# ACmonitor.net
KiCad netlist of a schematic drawn in Altium Designer
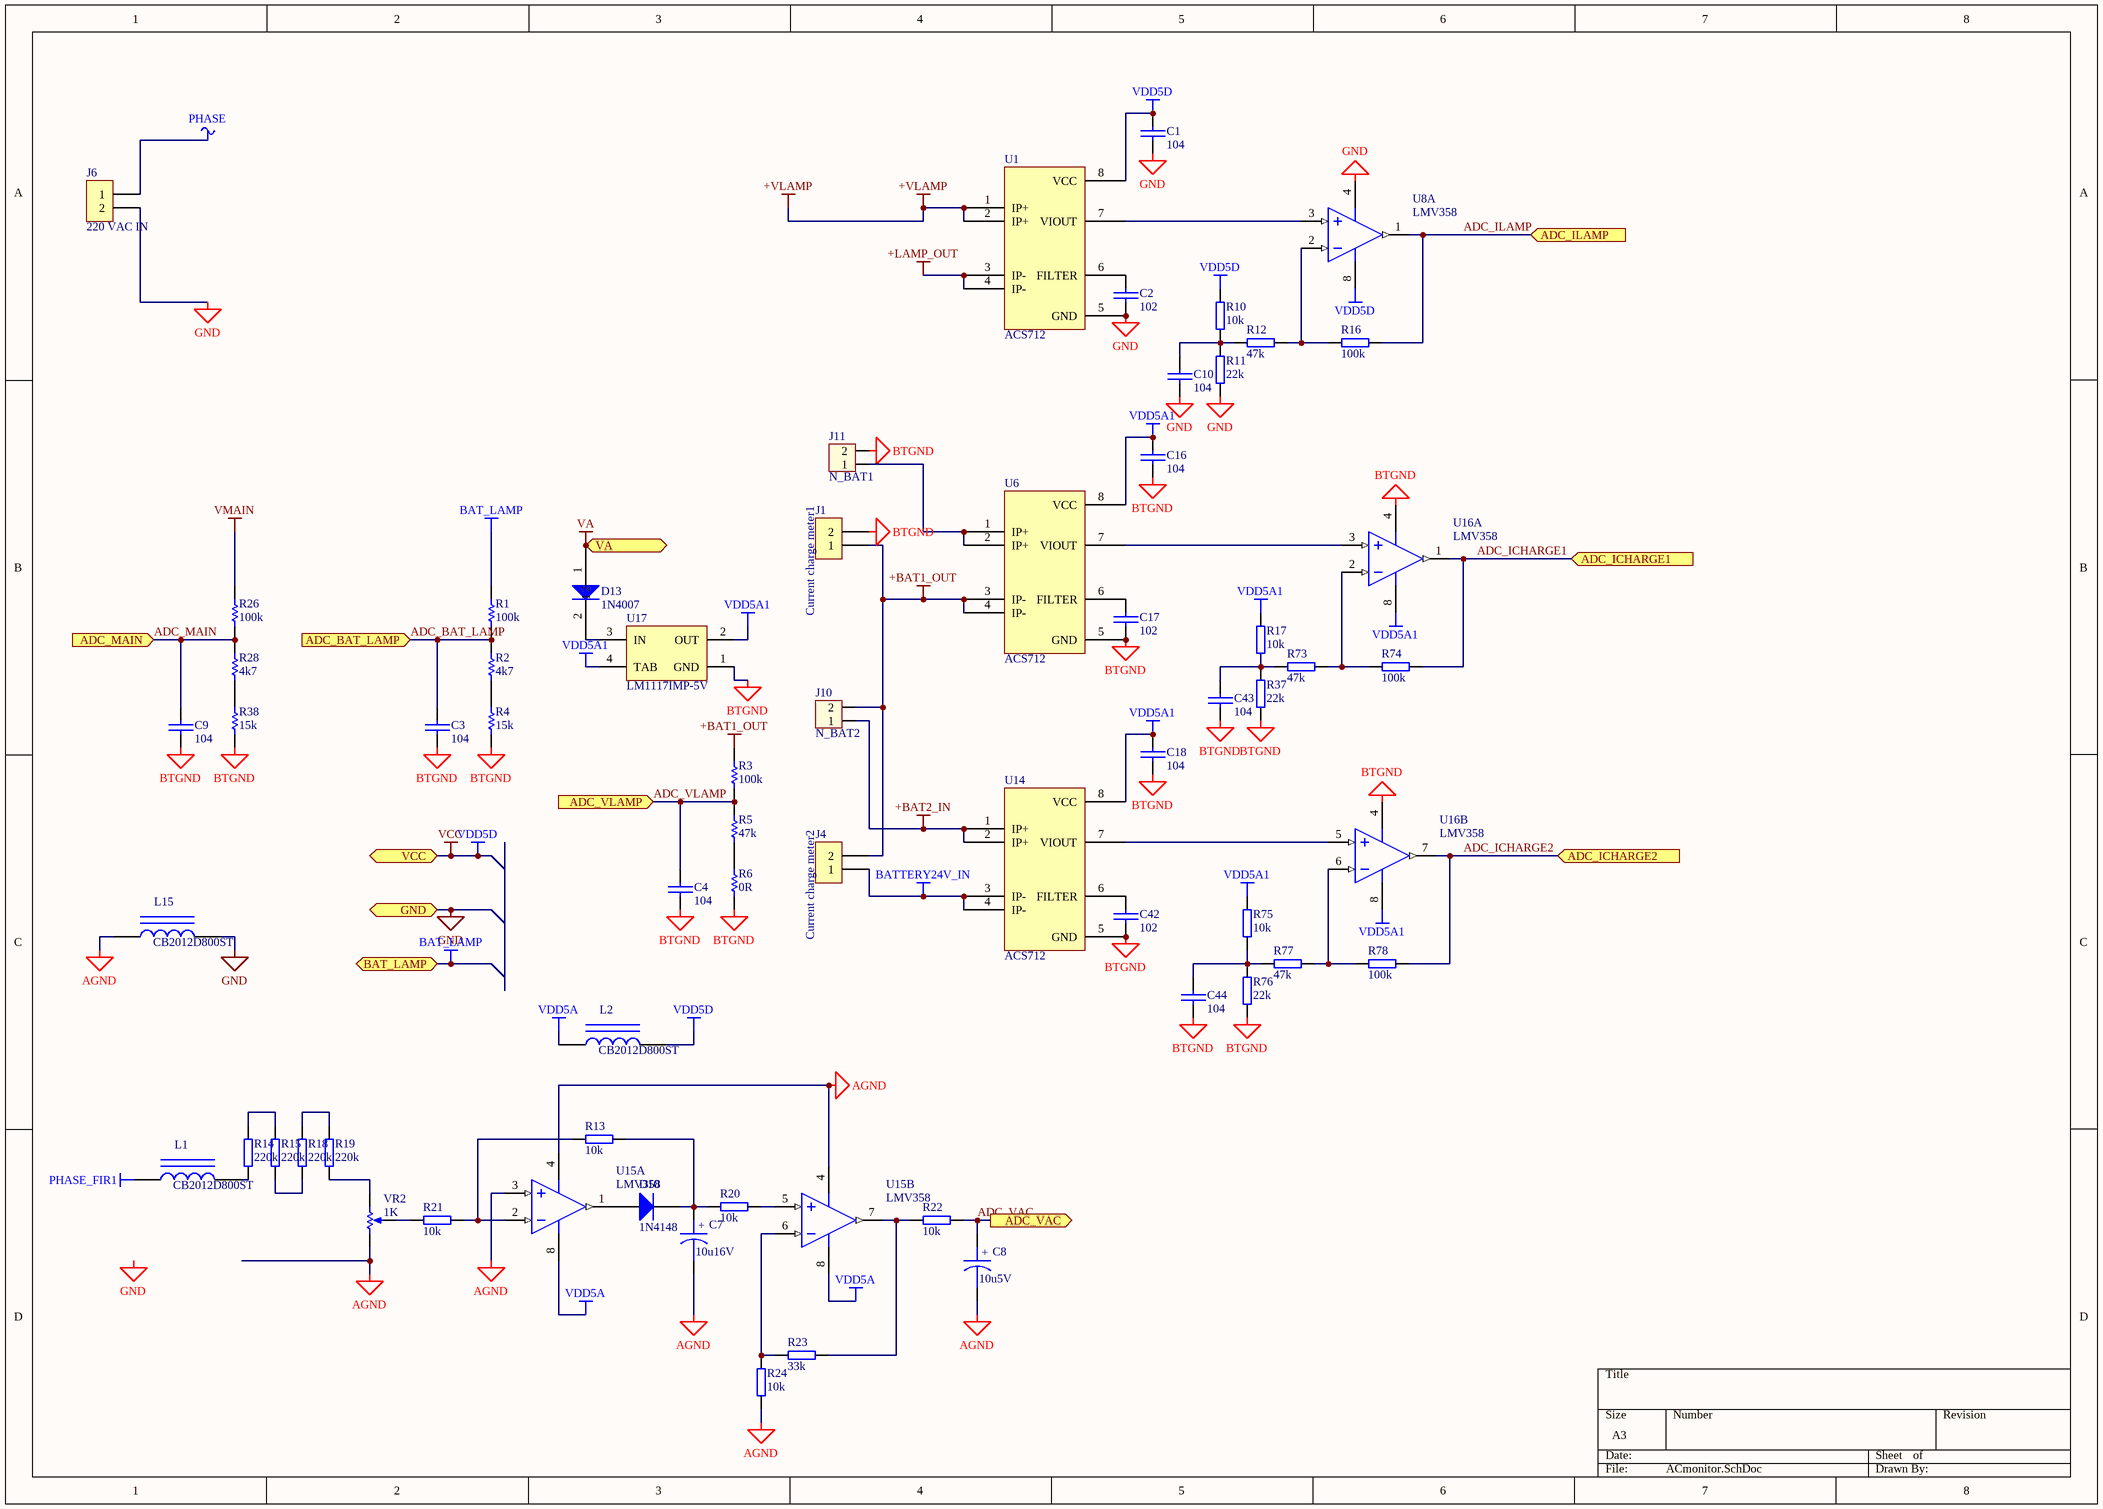
[diagram p0: ACmonitor.SchDoc]

(export (version "E")
  (design (tool "Eeschema 10.0.6"))
  (components
    (comp (ref "C1")
      (value "104")
      (footprint "C6-0805_N")
      (description "Capacitor")
      (libsource (lib "*") (part "CAP"))
    )
    (comp (ref "C2")
      (value "102")
      (footprint "C6-0805_N")
      (description "Capacitor")
      (libsource (lib "*") (part "CAP"))
    )
    (comp (ref "C3")
      (value "104")
      (footprint "C6-0805_N")
      (description "Capacitor")
      (libsource (lib "*") (part "CAP"))
    )
    (comp (ref "C4")
      (value "104")
      (footprint "C6-0805_N")
      (description "Capacitor")
      (libsource (lib "*") (part "CAP"))
    )
    (comp (ref "C7")
      (value "10u16V")
      (footprint "CAPMP7343X310N")
      (description "Capacitor")
      (libsource (lib "*") (part "CAPACITOR POL"))
    )
    (comp (ref "C8")
      (value "10u5V")
      (footprint "CAPMP3528X210N")
      (description "Capacitor")
      (libsource (lib "*") (part "CAPACITOR POL"))
    )
    (comp (ref "C9")
      (value "104")
      (footprint "C6-0805_N")
      (description "Capacitor")
      (libsource (lib "*") (part "CAP"))
    )
    (comp (ref "C10")
      (value "104")
      (footprint "C6-0805_N")
      (description "Capacitor")
      (libsource (lib "*") (part "CAP"))
    )
    (comp (ref "C16")
      (value "104")
      (footprint "C6-0805_N")
      (description "Capacitor")
      (libsource (lib "*") (part "CAP"))
    )
    (comp (ref "C17")
      (value "102")
      (footprint "C6-0805_N")
      (description "Capacitor")
      (libsource (lib "*") (part "CAP"))
    )
    (comp (ref "C18")
      (value "104")
      (footprint "C6-0805_N")
      (description "Capacitor")
      (libsource (lib "*") (part "CAP"))
    )
    (comp (ref "C42")
      (value "102")
      (footprint "C6-0805_N")
      (description "Capacitor")
      (libsource (lib "*") (part "CAP"))
    )
    (comp (ref "C43")
      (value "104")
      (footprint "C6-0805_N")
      (description "Capacitor")
      (libsource (lib "*") (part "CAP"))
    )
    (comp (ref "C44")
      (value "104")
      (footprint "C6-0805_N")
      (description "Capacitor")
      (libsource (lib "*") (part "CAP"))
    )
    (comp (ref "D10")
      (value "1N4148")
      (footprint "SOD80, LL-34")
      (description "1 Amp General Purpose Rectifier")
      (fields (field (name "PUBLISHER") "Altium Limited"))
      (libsource (lib "*") (part "Diode 1N4007"))
    )
    (comp (ref "D13") (value "1N4007") (footprint "DO-214AA") (libsource (lib "*") (part "DIODE")))
    (comp (ref "J1")
      (value "Current charge meter1")
      (footprint "TERMINAL2")
      (description "Connector")
      (libsource (lib "") (part "CON2_1"))
    )
    (comp (ref "J4")
      (value "Current charge meter2")
      (footprint "TERMINAL2")
      (description "Connector")
      (libsource (lib "") (part "CON2_1"))
    )
    (comp (ref "J6")
      (value "220 VAC IN")
      (footprint "TERMINAL2")
      (description "Connector")
      (libsource (lib "*") (part "CON2"))
    )
    (comp (ref "J10")
      (value "N_BAT2")
      (footprint "TERMINAL2")
      (description "Connector 2")
      (libsource (lib "syhaunguyen") (part "Con2"))
    )
    (comp (ref "J11")
      (value "N_BAT1")
      (footprint "TERMINAL2")
      (description "Connector 2")
      (libsource (lib "syhaunguyen") (part "Con2"))
    )
    (comp (ref "L1")
      (value "CB2012D800ST")
      (footprint "R6-0805_N")
      (description "80 Ohm SMD-0805 Chip Ferrite Bead")
      (libsource (lib "*") (part "INDUCTOR IRON"))
    )
    (comp (ref "L2")
      (value "CB2012D800ST")
      (footprint "R6-0805_N")
      (description "80 Ohm SMD-0805 Chip Ferrite Bead")
      (libsource (lib "*") (part "INDUCTOR IRON"))
    )
    (comp (ref "L15")
      (value "CB2012D800ST")
      (footprint "R6-0805_N")
      (description "80 Ohm SMD-0805 Chip Ferrite Bead")
      (libsource (lib "*") (part "INDUCTOR IRON"))
    )
    (comp (ref "R1")
      (value "100k")
      (footprint "6-0805_N")
      (description "Semiconductor Resistor")
      (fields (field (name "PUBLISHER") "*"))
      (libsource (lib "*") (part "Res Semi"))
    )
    (comp (ref "R2")
      (value "4k7")
      (footprint "6-0805_N")
      (description "Semiconductor Resistor")
      (fields (field (name "PUBLISHER") "*"))
      (libsource (lib "*") (part "Res Semi"))
    )
    (comp (ref "R3")
      (value "100k")
      (footprint "6-0805_N")
      (description "Semiconductor Resistor")
      (fields (field (name "PUBLISHER") "*"))
      (libsource (lib "*") (part "Res Semi"))
    )
    (comp (ref "R4")
      (value "15k")
      (footprint "6-0805_N")
      (description "Semiconductor Resistor")
      (fields (field (name "PUBLISHER") "*"))
      (libsource (lib "*") (part "Res Semi"))
    )
    (comp (ref "R5")
      (value "47k")
      (footprint "6-0805_N")
      (description "Semiconductor Resistor")
      (fields (field (name "PUBLISHER") "*"))
      (libsource (lib "*") (part "Res Semi"))
    )
    (comp (ref "R6")
      (value "0R")
      (footprint "6-0805_N")
      (description "Semiconductor Resistor")
      (fields (field (name "PUBLISHER") "*"))
      (libsource (lib "*") (part "Res Semi"))
    )
    (comp (ref "R10") (value "10k") (footprint "6-0805_N") (libsource (lib "*") (part "RES2")))
    (comp (ref "R11") (value "22k") (footprint "6-0805_N") (libsource (lib "*") (part "RES2")))
    (comp (ref "R12") (value "47k") (footprint "6-0805_N") (libsource (lib "*") (part "RES2")))
    (comp (ref "R13") (value "10k") (footprint "6-0805_N") (libsource (lib "*") (part "RES2")))
    (comp (ref "R14") (value "220k") (footprint "R3216[1206]") (libsource (lib "*") (part "RES2")))
    (comp (ref "R15") (value "220k") (footprint "R3216[1206]") (libsource (lib "*") (part "RES2")))
    (comp (ref "R16") (value "100k") (footprint "6-0805_N") (libsource (lib "*") (part "RES2")))
    (comp (ref "R17") (value "10k") (footprint "6-0805_N") (libsource (lib "*") (part "RES2")))
    (comp (ref "R18") (value "220k") (footprint "R3216[1206]") (libsource (lib "*") (part "RES2")))
    (comp (ref "R19") (value "220k") (footprint "R3216[1206]") (libsource (lib "*") (part "RES2")))
    (comp (ref "R20") (value "10k") (footprint "6-0805_N") (libsource (lib "*") (part "RES2")))
    (comp (ref "R21") (value "10k") (footprint "6-0805_N") (libsource (lib "*") (part "RES2")))
    (comp (ref "R22") (value "10k") (footprint "6-0805_N") (libsource (lib "*") (part "RES2")))
    (comp (ref "R23") (value "33k") (footprint "6-0805_N") (libsource (lib "*") (part "RES2")))
    (comp (ref "R24") (value "10k") (footprint "6-0805_N") (libsource (lib "*") (part "RES2")))
    (comp (ref "R26")
      (value "100k")
      (footprint "6-0805_N")
      (description "Semiconductor Resistor")
      (fields (field (name "PUBLISHER") "*"))
      (libsource (lib "*") (part "Res Semi"))
    )
    (comp (ref "R28")
      (value "4k7")
      (footprint "6-0805_N")
      (description "Semiconductor Resistor")
      (fields (field (name "PUBLISHER") "*"))
      (libsource (lib "*") (part "Res Semi"))
    )
    (comp (ref "R37") (value "22k") (footprint "6-0805_N") (libsource (lib "*") (part "RES2")))
    (comp (ref "R38")
      (value "15k")
      (footprint "6-0805_N")
      (description "Semiconductor Resistor")
      (fields (field (name "PUBLISHER") "*"))
      (libsource (lib "*") (part "Res Semi"))
    )
    (comp (ref "R73") (value "47k") (footprint "6-0805_N") (libsource (lib "*") (part "RES2")))
    (comp (ref "R74") (value "100k") (footprint "6-0805_N") (libsource (lib "*") (part "RES2")))
    (comp (ref "R75") (value "10k") (footprint "6-0805_N") (libsource (lib "*") (part "RES2")))
    (comp (ref "R76") (value "22k") (footprint "6-0805_N") (libsource (lib "*") (part "RES2")))
    (comp (ref "R77") (value "47k") (footprint "6-0805_N") (libsource (lib "*") (part "RES2")))
    (comp (ref "R78") (value "100k") (footprint "6-0805_N") (libsource (lib "*") (part "RES2")))
    (comp (ref "U1") (value "ACS712") (footprint "M08A_N") (libsource (lib "Schlib1") (part "ACS712")))
    (comp (ref "U6") (value "ACS712") (footprint "M08A_N") (libsource (lib "Schlib1") (part "ACS712")))
    (comp (ref "U8")
      (value "LMV358")
      (footprint "M08A_N")
      (description "Low Power Dual Operational Amplifier, 8-pin Narrow SOIC")
      (fields
        (field (name "PARTNUMBER") "LM358AM")
        (field (name "MANUFACTURER") "National Semiconductor")
        (field (name "PUBLISHER") "Altium Limited")
      )
      (libsource (lib "NSC Amplifier") (part "LM358AM"))
    )
    (comp (ref "U14") (value "ACS712") (footprint "M08A_N") (libsource (lib "Schlib1") (part "ACS712")))
    (comp (ref "U15")
      (value "LMV358")
      (footprint "M08A_N")
      (description "Low Power Dual Operational Amplifier, 8-pin Narrow SOIC")
      (fields
        (field (name "PARTNUMBER") "LM358AM")
        (field (name "MANUFACTURER") "National Semiconductor")
        (field (name "PUBLISHER") "Altium Limited")
      )
      (libsource (lib "NSC Amplifier") (part "LM358AM"))
    )
    (comp (ref "U16")
      (value "LMV358")
      (footprint "M08A_N")
      (description "Low Power Dual Operational Amplifier, 8-pin Narrow SOIC")
      (fields
        (field (name "PARTNUMBER") "LM358AM")
        (field (name "MANUFACTURER") "National Semiconductor")
        (field (name "PUBLISHER") "Altium Limited")
      )
      (libsource (lib "NSC Amplifier") (part "LM358AM"))
    )
    (comp (ref "U17")
      (value "LM1117IMP-5V")
      (footprint "MP04A_N")
      (description "800mA Low-Dropout Linear Regulator, 4-pin SOT-223")
      (fields
        (field (name "PARTNUMBER") "LM1117IMP-3.3")
        (field (name "MANUFACTURER") "National Semiconductor")
        (field (name "PUBLISHER") "Altium Limited")
      )
      (libsource (lib "NSC LDO") (part "LM1117IMP-3.3"))
    )
    (comp (ref "VR2")
      (value "1K")
      (footprint "BTXANH")
      (description "Potentiometer")
      (fields (field (name "PUBLISHER") "*"))
      (libsource (lib "*") (part "RPot"))
    )
  )
  (nets
    (net (code "1") (name "+BAT1_OUT") (class "Default")
      (node (ref "J1") (pin "1") (pinfunction "1_1") (pintype "passive"))
      (node (ref "J10") (pin "2") (pinfunction "2_2") (pintype "passive"))
      (node (ref "J4") (pin "2") (pinfunction "2_2") (pintype "passive"))
      (node (ref "R3") (pin "1") (pinfunction "1_1") (pintype "passive"))
      (node (ref "U6") (pin "3") (pinfunction "IP-_3") (pintype "passive"))
      (node (ref "U6") (pin "4") (pinfunction "IP-_4") (pintype "passive"))
    )
    (net (code "2") (name "+BAT2_IN") (class "Default")
      (node (ref "J10") (pin "1") (pinfunction "1_1") (pintype "passive"))
      (node (ref "U14") (pin "1") (pinfunction "IP+_1") (pintype "passive"))
      (node (ref "U14") (pin "2") (pinfunction "IP+_2") (pintype "passive"))
    )
    (net (code "3") (name "+LAMP_OUT") (class "Default")
      (node (ref "U1") (pin "3") (pinfunction "IP-_3") (pintype "passive"))
      (node (ref "U1") (pin "4") (pinfunction "IP-_4") (pintype "passive"))
    )
    (net (code "4") (name "+VLAMP") (class "Default")
      (node (ref "U1") (pin "1") (pinfunction "IP+_1") (pintype "passive"))
      (node (ref "U1") (pin "2") (pinfunction "IP+_2") (pintype "passive"))
    )
    (net (code "5") (name "/ADC_BAT_LAMP") (class "Default")
      (node (ref "C3") (pin "1") (pinfunction "1_1") (pintype "passive"))
      (node (ref "R1") (pin "2") (pinfunction "2_2") (pintype "passive"))
      (node (ref "R2") (pin "1") (pinfunction "1_1") (pintype "passive"))
    )
    (net (code "6") (name "/ADC_ICHARGE1") (class "Default")
      (node (ref "R74") (pin "2") (pinfunction "2_2") (pintype "passive"))
      (node (ref "U16") (pin "1") (pinfunction "OUTA_1") (pintype "output"))
    )
    (net (code "7") (name "/ADC_ICHARGE2") (class "Default")
      (node (ref "R78") (pin "2") (pinfunction "2_2") (pintype "passive"))
      (node (ref "U16") (pin "7") (pinfunction "OUTB_7") (pintype "output"))
    )
    (net (code "8") (name "/ADC_ILAMP") (class "Default")
      (node (ref "R16") (pin "2") (pinfunction "2_2") (pintype "passive"))
      (node (ref "U8") (pin "1") (pinfunction "OUTA_1") (pintype "output"))
    )
    (net (code "9") (name "/ADC_MAIN") (class "Default")
      (node (ref "C9") (pin "1") (pinfunction "1_1") (pintype "passive"))
      (node (ref "R26") (pin "2") (pinfunction "2_2") (pintype "passive"))
      (node (ref "R28") (pin "1") (pinfunction "1_1") (pintype "passive"))
    )
    (net (code "10") (name "/ADC_VAC") (class "Default")
      (node (ref "C8") (pin "1") (pinfunction "1_1") (pintype "passive"))
      (node (ref "R22") (pin "1") (pinfunction "1_1") (pintype "passive"))
    )
    (net (code "11") (name "/ADC_VLAMP") (class "Default")
      (node (ref "C4") (pin "1") (pinfunction "1_1") (pintype "passive"))
      (node (ref "R3") (pin "2") (pinfunction "2_2") (pintype "passive"))
      (node (ref "R5") (pin "1") (pinfunction "1_1") (pintype "passive"))
    )
    (net (code "12") (name "AGND") (class "Default")
      (node (ref "C7") (pin "2") (pinfunction "2_2") (pintype "passive"))
      (node (ref "C8") (pin "2") (pinfunction "2_2") (pintype "passive"))
      (node (ref "L15") (pin "1") (pinfunction "1_1") (pintype "passive"))
      (node (ref "R24") (pin "2") (pinfunction "2_2") (pintype "passive"))
      (node (ref "U15") (pin "3") (pinfunction "INA+_3") (pintype "input"))
      (node (ref "U15") (pin "4") (pinfunction "GND_4") (pintype "power_in"))
      (node (ref "VR2") (pin "1") (pinfunction "TOP_1") (pintype "passive"))
    )
    (net (code "13") (name "BATTERY24V_IN") (class "Default")
      (node (ref "J4") (pin "1") (pinfunction "1_1") (pintype "passive"))
      (node (ref "U14") (pin "3") (pinfunction "IP-_3") (pintype "passive"))
      (node (ref "U14") (pin "4") (pinfunction "IP-_4") (pintype "passive"))
    )
    (net (code "14") (name "BAT_LAMP") (class "Default")
      (node (ref "R1") (pin "1") (pinfunction "1_1") (pintype "passive"))
    )
    (net (code "15") (name "BTGND") (class "Default")
      (node (ref "C16") (pin "2") (pinfunction "2_2") (pintype "passive"))
      (node (ref "C17") (pin "2") (pinfunction "2_2") (pintype "passive"))
      (node (ref "C18") (pin "2") (pinfunction "2_2") (pintype "passive"))
      (node (ref "C3") (pin "2") (pinfunction "2_2") (pintype "passive"))
      (node (ref "C4") (pin "2") (pinfunction "2_2") (pintype "passive"))
      (node (ref "C42") (pin "2") (pinfunction "2_2") (pintype "passive"))
      (node (ref "C43") (pin "2") (pinfunction "2_2") (pintype "passive"))
      (node (ref "C44") (pin "2") (pinfunction "2_2") (pintype "passive"))
      (node (ref "C9") (pin "2") (pinfunction "2_2") (pintype "passive"))
      (node (ref "J1") (pin "2") (pinfunction "2_2") (pintype "passive"))
      (node (ref "J11") (pin "2") (pinfunction "2_2") (pintype "passive"))
      (node (ref "R37") (pin "2") (pinfunction "2_2") (pintype "passive"))
      (node (ref "R38") (pin "2") (pinfunction "2_2") (pintype "passive"))
      (node (ref "R4") (pin "2") (pinfunction "2_2") (pintype "passive"))
      (node (ref "R6") (pin "2") (pinfunction "2_2") (pintype "passive"))
      (node (ref "R76") (pin "2") (pinfunction "2_2") (pintype "passive"))
      (node (ref "U14") (pin "5") (pinfunction "GND_5") (pintype "passive"))
      (node (ref "U16") (pin "4") (pinfunction "GND_4") (pintype "power_in"))
      (node (ref "U17") (pin "1") (pinfunction "GND_1") (pintype "power_in"))
      (node (ref "U6") (pin "5") (pinfunction "GND_5") (pintype "passive"))
    )
    (net (code "16") (name "GND") (class "Default")
      (node (ref "C1") (pin "2") (pinfunction "2_2") (pintype "passive"))
      (node (ref "C10") (pin "2") (pinfunction "2_2") (pintype "passive"))
      (node (ref "C2") (pin "2") (pinfunction "2_2") (pintype "passive"))
      (node (ref "J6") (pin "2") (pinfunction "2_2") (pintype "passive"))
      (node (ref "L15") (pin "2") (pinfunction "2_2") (pintype "passive"))
      (node (ref "R11") (pin "2") (pinfunction "2_2") (pintype "passive"))
      (node (ref "U1") (pin "5") (pinfunction "GND_5") (pintype "passive"))
      (node (ref "U8") (pin "4") (pinfunction "GND_4") (pintype "power_in"))
    )
    (net (code "17") (name "Net-(C10-Pad1)") (class "Default")
      (node (ref "C10") (pin "1") (pinfunction "1_1") (pintype "passive"))
      (node (ref "R10") (pin "1") (pinfunction "1_1") (pintype "passive"))
      (node (ref "R11") (pin "1") (pinfunction "1_1") (pintype "passive"))
      (node (ref "R12") (pin "2") (pinfunction "2_2") (pintype "passive"))
    )
    (net (code "18") (name "Net-(C43-Pad1)") (class "Default")
      (node (ref "C43") (pin "1") (pinfunction "1_1") (pintype "passive"))
      (node (ref "R17") (pin "1") (pinfunction "1_1") (pintype "passive"))
      (node (ref "R37") (pin "1") (pinfunction "1_1") (pintype "passive"))
      (node (ref "R73") (pin "2") (pinfunction "2_2") (pintype "passive"))
    )
    (net (code "19") (name "Net-(C44-Pad1)") (class "Default")
      (node (ref "C44") (pin "1") (pinfunction "1_1") (pintype "passive"))
      (node (ref "R75") (pin "2") (pinfunction "2_2") (pintype "passive"))
      (node (ref "R76") (pin "1") (pinfunction "1_1") (pintype "passive"))
      (node (ref "R77") (pin "2") (pinfunction "2_2") (pintype "passive"))
    )
    (net (code "20") (name "Net-(D10-A)") (class "Default")
      (node (ref "D10") (pin "1") (pinfunction "A_1") (pintype "passive"))
      (node (ref "U15") (pin "1") (pinfunction "OUTA_1") (pintype "output"))
    )
    (net (code "21") (name "Net-(D10-K)") (class "Default")
      (node (ref "C7") (pin "1") (pinfunction "1_1") (pintype "passive"))
      (node (ref "D10") (pin "2") (pinfunction "K_2") (pintype "passive"))
      (node (ref "R13") (pin "1") (pinfunction "1_1") (pintype "passive"))
      (node (ref "R20") (pin "2") (pinfunction "2_2") (pintype "passive"))
    )
    (net (code "22") (name "Net-(J11-Pad1)") (class "Default")
      (node (ref "J11") (pin "1") (pinfunction "1_1") (pintype "passive"))
      (node (ref "U6") (pin "1") (pinfunction "IP+_1") (pintype "passive"))
      (node (ref "U6") (pin "2") (pinfunction "IP+_2") (pintype "passive"))
    )
    (net (code "23") (name "Net-(L1-Pad2)") (class "Default")
      (node (ref "L1") (pin "2") (pinfunction "2_2") (pintype "passive"))
      (node (ref "R14") (pin "2") (pinfunction "2_2") (pintype "passive"))
    )
    (net (code "24") (name "Net-(R2-Pad2)") (class "Default")
      (node (ref "R2") (pin "2") (pinfunction "2_2") (pintype "passive"))
      (node (ref "R4") (pin "1") (pinfunction "1_1") (pintype "passive"))
    )
    (net (code "25") (name "Net-(R5-Pad2)") (class "Default")
      (node (ref "R5") (pin "2") (pinfunction "2_2") (pintype "passive"))
      (node (ref "R6") (pin "1") (pinfunction "1_1") (pintype "passive"))
    )
    (net (code "26") (name "Net-(R14-Pad1)") (class "Default")
      (node (ref "R14") (pin "1") (pinfunction "1_1") (pintype "passive"))
      (node (ref "R15") (pin "1") (pinfunction "1_1") (pintype "passive"))
    )
    (net (code "27") (name "Net-(R15-Pad2)") (class "Default")
      (node (ref "R15") (pin "2") (pinfunction "2_2") (pintype "passive"))
      (node (ref "R18") (pin "2") (pinfunction "2_2") (pintype "passive"))
    )
    (net (code "28") (name "Net-(R18-Pad1)") (class "Default")
      (node (ref "R18") (pin "1") (pinfunction "1_1") (pintype "passive"))
      (node (ref "R19") (pin "1") (pinfunction "1_1") (pintype "passive"))
    )
    (net (code "29") (name "Net-(R28-Pad2)") (class "Default")
      (node (ref "R28") (pin "2") (pinfunction "2_2") (pintype "passive"))
      (node (ref "R38") (pin "1") (pinfunction "1_1") (pintype "passive"))
    )
    (net (code "30") (name "Net-(U1-FILTER)") (class "Default")
      (node (ref "C2") (pin "1") (pinfunction "1_1") (pintype "passive"))
      (node (ref "U1") (pin "6") (pinfunction "FILTER_6") (pintype "passive"))
    )
    (net (code "31") (name "Net-(U1-VIOUT)") (class "Default")
      (node (ref "U1") (pin "7") (pinfunction "VIOUT_7") (pintype "passive"))
      (node (ref "U8") (pin "3") (pinfunction "INA+_3") (pintype "input"))
    )
    (net (code "32") (name "Net-(U6-FILTER)") (class "Default")
      (node (ref "C17") (pin "1") (pinfunction "1_1") (pintype "passive"))
      (node (ref "U6") (pin "6") (pinfunction "FILTER_6") (pintype "passive"))
    )
    (net (code "33") (name "Net-(U8A-INA-)") (class "Default")
      (node (ref "R12") (pin "1") (pinfunction "1_1") (pintype "passive"))
      (node (ref "R16") (pin "1") (pinfunction "1_1") (pintype "passive"))
      (node (ref "U8") (pin "2") (pinfunction "INA-_2") (pintype "input"))
    )
    (net (code "34") (name "Net-(U14-FILTER)") (class "Default")
      (node (ref "C42") (pin "1") (pinfunction "1_1") (pintype "passive"))
      (node (ref "U14") (pin "6") (pinfunction "FILTER_6") (pintype "passive"))
    )
    (net (code "35") (name "Net-(U14-VIOUT)") (class "Default")
      (node (ref "U14") (pin "7") (pinfunction "VIOUT_7") (pintype "passive"))
      (node (ref "U16") (pin "5") (pinfunction "INB+_5") (pintype "input"))
    )
    (net (code "36") (name "Net-(U15A-INA-)") (class "Default")
      (node (ref "R13") (pin "2") (pinfunction "2_2") (pintype "passive"))
      (node (ref "R21") (pin "1") (pinfunction "1_1") (pintype "passive"))
      (node (ref "U15") (pin "2") (pinfunction "INA-_2") (pintype "input"))
    )
    (net (code "37") (name "Net-(U15B-INB+)") (class "Default")
      (node (ref "R20") (pin "1") (pinfunction "1_1") (pintype "passive"))
      (node (ref "U15") (pin "5") (pinfunction "INB+_5") (pintype "input"))
    )
    (net (code "38") (name "Net-(U15B-INB-)") (class "Default")
      (node (ref "R23") (pin "2") (pinfunction "2_2") (pintype "passive"))
      (node (ref "R24") (pin "1") (pinfunction "1_1") (pintype "passive"))
      (node (ref "U15") (pin "6") (pinfunction "INB-_6") (pintype "input"))
    )
    (net (code "39") (name "Net-(U15B-OUTB)") (class "Default")
      (node (ref "R22") (pin "2") (pinfunction "2_2") (pintype "passive"))
      (node (ref "R23") (pin "1") (pinfunction "1_1") (pintype "passive"))
      (node (ref "U15") (pin "7") (pinfunction "OUTB_7") (pintype "output"))
    )
    (net (code "40") (name "Net-(U16A-INA+)") (class "Default")
      (node (ref "U16") (pin "3") (pinfunction "INA+_3") (pintype "input"))
      (node (ref "U6") (pin "7") (pinfunction "VIOUT_7") (pintype "passive"))
    )
    (net (code "41") (name "Net-(U16A-INA-)") (class "Default")
      (node (ref "R73") (pin "1") (pinfunction "1_1") (pintype "passive"))
      (node (ref "R74") (pin "1") (pinfunction "1_1") (pintype "passive"))
      (node (ref "U16") (pin "2") (pinfunction "INA-_2") (pintype "input"))
    )
    (net (code "42") (name "Net-(U16B-INB-)") (class "Default")
      (node (ref "R77") (pin "1") (pinfunction "1_1") (pintype "passive"))
      (node (ref "R78") (pin "1") (pinfunction "1_1") (pintype "passive"))
      (node (ref "U16") (pin "6") (pinfunction "INB-_6") (pintype "input"))
    )
    (net (code "43") (name "Net-(U17-IN)") (class "Default")
      (node (ref "D13") (pin "2") (pinfunction "2_2") (pintype "passive"))
      (node (ref "U17") (pin "3") (pinfunction "IN_3") (pintype "power_in"))
    )
    (net (code "44") (name "Net-(VR2-BOT)") (class "Default")
      (node (ref "R19") (pin "2") (pinfunction "2_2") (pintype "passive"))
      (node (ref "VR2") (pin "3") (pinfunction "BOT_3") (pintype "passive"))
    )
    (net (code "45") (name "Net-(VR2-TAP)") (class "Default")
      (node (ref "R21") (pin "2") (pinfunction "2_2") (pintype "passive"))
      (node (ref "VR2") (pin "2") (pinfunction "TAP_2") (pintype "passive"))
    )
    (net (code "46") (name "PHASE") (class "Default")
      (node (ref "J6") (pin "1") (pinfunction "1_1") (pintype "passive"))
    )
    (net (code "47") (name "PHASE_FIR1") (class "Default")
      (node (ref "L1") (pin "1") (pinfunction "1_1") (pintype "passive"))
    )
    (net (code "48") (name "VA") (class "Default")
      (node (ref "D13") (pin "1") (pinfunction "1_1") (pintype "passive"))
    )
    (net (code "49") (name "VCC") (class "Default")
      (node (ref "C1") (pin "1") (pinfunction "1_1") (pintype "passive"))
      (node (ref "L2") (pin "2") (pinfunction "2_2") (pintype "passive"))
      (node (ref "R10") (pin "2") (pinfunction "2_2") (pintype "passive"))
      (node (ref "U1") (pin "8") (pinfunction "VCC_8") (pintype "passive"))
      (node (ref "U8") (pin "8") (pinfunction "V+_8") (pintype "power_in"))
    )
    (net (code "50") (name "VDD5A") (class "Default")
      (node (ref "L2") (pin "1") (pinfunction "1_1") (pintype "passive"))
      (node (ref "U15") (pin "8") (pinfunction "V+_8") (pintype "power_in"))
    )
    (net (code "51") (name "VDD5A1") (class "Default")
      (node (ref "C16") (pin "1") (pinfunction "1_1") (pintype "passive"))
      (node (ref "C18") (pin "1") (pinfunction "1_1") (pintype "passive"))
      (node (ref "R17") (pin "2") (pinfunction "2_2") (pintype "passive"))
      (node (ref "R75") (pin "1") (pinfunction "1_1") (pintype "passive"))
      (node (ref "U14") (pin "8") (pinfunction "VCC_8") (pintype "passive"))
      (node (ref "U16") (pin "8") (pinfunction "V+_8") (pintype "power_in"))
      (node (ref "U17") (pin "2") (pinfunction "OUT_2") (pintype "power_in"))
      (node (ref "U17") (pin "4") (pinfunction "TAB_4") (pintype "power_in"))
      (node (ref "U6") (pin "8") (pinfunction "VCC_8") (pintype "passive"))
    )
    (net (code "52") (name "VMAIN") (class "Default")
      (node (ref "R26") (pin "1") (pinfunction "1_1") (pintype "passive"))
    )
  )
)
